# Proto-v2_1_-_TO-92.net
KiCad netlist of a schematic drawn in EAGLE
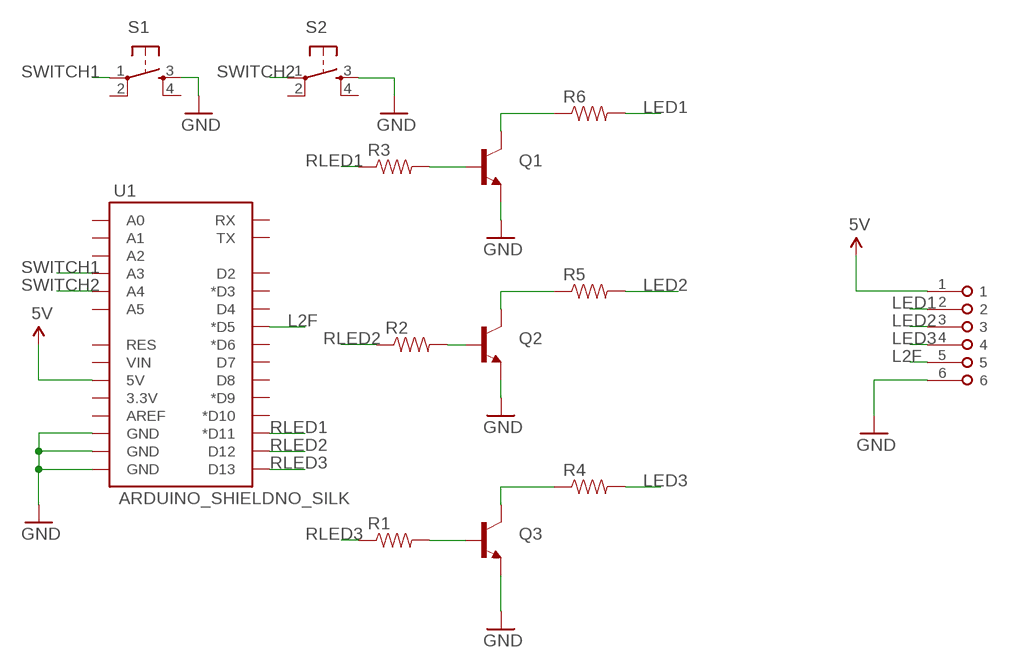
[diagram p0: schematic, sheet 1]

(export (version "E")
  (design (tool "Eeschema 10.0.6"))
  (components
    (comp (ref "Q1")
      (value "TRANSISTOR_NPNBC547")
      (footprint "eagle-import:TO-92-AMMO")
      (libsource (lib "eagle-import") (part "TRANSISTOR_NPNBC547"))
    )
    (comp (ref "Q2")
      (value "TRANSISTOR_NPNBC547")
      (footprint "eagle-import:TO-92-AMMO")
      (libsource (lib "eagle-import") (part "TRANSISTOR_NPNBC547"))
    )
    (comp (ref "Q3")
      (value "TRANSISTOR_NPNBC547")
      (footprint "eagle-import:TO-92-AMMO")
      (libsource (lib "eagle-import") (part "TRANSISTOR_NPNBC547"))
    )
    (comp (ref "R1")
      (value "RESISTORAXIAL-0.3")
      (footprint "eagle-import:AXIAL-0.3")
      (libsource (lib "eagle-import") (part "RESISTORAXIAL-0.3"))
    )
    (comp (ref "R2")
      (value "RESISTORAXIAL-0.3")
      (footprint "eagle-import:AXIAL-0.3")
      (libsource (lib "eagle-import") (part "RESISTORAXIAL-0.3"))
    )
    (comp (ref "R3")
      (value "RESISTORAXIAL-0.3")
      (footprint "eagle-import:AXIAL-0.3")
      (libsource (lib "eagle-import") (part "RESISTORAXIAL-0.3"))
    )
    (comp (ref "R4")
      (value "RESISTORAXIAL-0.3")
      (footprint "eagle-import:AXIAL-0.3")
      (libsource (lib "eagle-import") (part "RESISTORAXIAL-0.3"))
    )
    (comp (ref "R5")
      (value "RESISTORAXIAL-0.3")
      (footprint "eagle-import:AXIAL-0.3")
      (libsource (lib "eagle-import") (part "RESISTORAXIAL-0.3"))
    )
    (comp (ref "R6")
      (value "RESISTORAXIAL-0.3")
      (footprint "eagle-import:AXIAL-0.3")
      (libsource (lib "eagle-import") (part "RESISTORAXIAL-0.3"))
    )
    (comp (ref "S1")
      (value "TAC_SWITCHPTH")
      (footprint "eagle-import:TACTILE-PTH")
      (libsource (lib "eagle-import") (part "TAC_SWITCHPTH"))
    )
    (comp (ref "S2")
      (value "TAC_SWITCHPTH")
      (footprint "eagle-import:TACTILE-PTH")
      (libsource (lib "eagle-import") (part "TAC_SWITCHPTH"))
    )
    (comp (ref "U$1")
      (value "TERMINAL-6")
      (footprint "eagle-import:MBE-156")
      (libsource (lib "eagle-import") (part "TERMINAL-6"))
    )
    (comp (ref "U1")
      (value "ARDUINO_SHIELDNO_SILK")
      (footprint "eagle-import:DUEMILANOVE_VIAS")
      (libsource (lib "eagle-import") (part "ARDUINO_SHIELDNO_SILK"))
    )
  )
  (nets
    (net (code "1") (name "/L2F") (class "Default")
      (node (ref "U$1") (pin "5") (pinfunction "5_5") (pintype "bidirectional"))
      (node (ref "U1") (pin "D5") (pinfunction "*D5_D5") (pintype "bidirectional"))
    )
    (net (code "2") (name "/LED1") (class "Default")
      (node (ref "R6") (pin "P$2") (pinfunction "2_P$2") (pintype "passive"))
      (node (ref "U$1") (pin "2") (pinfunction "2_2") (pintype "bidirectional"))
    )
    (net (code "3") (name "/LED2") (class "Default")
      (node (ref "R5") (pin "P$2") (pinfunction "2_P$2") (pintype "passive"))
      (node (ref "U$1") (pin "3") (pinfunction "3_3") (pintype "bidirectional"))
    )
    (net (code "4") (name "/LED3") (class "Default")
      (node (ref "R4") (pin "P$2") (pinfunction "2_P$2") (pintype "passive"))
      (node (ref "U$1") (pin "4") (pinfunction "4_4") (pintype "bidirectional"))
    )
    (net (code "5") (name "/RLED1") (class "Default")
      (node (ref "R3") (pin "P$1") (pinfunction "1_P$1") (pintype "passive"))
      (node (ref "U1") (pin "D11") (pinfunction "*D11_D11") (pintype "bidirectional"))
    )
    (net (code "6") (name "/RLED2") (class "Default")
      (node (ref "R2") (pin "P$1") (pinfunction "1_P$1") (pintype "passive"))
      (node (ref "U1") (pin "D12") (pinfunction "D12_D12") (pintype "bidirectional"))
    )
    (net (code "7") (name "/RLED3") (class "Default")
      (node (ref "R1") (pin "P$1") (pinfunction "1_P$1") (pintype "passive"))
      (node (ref "U1") (pin "D13") (pinfunction "D13_D13") (pintype "bidirectional"))
    )
    (net (code "8") (name "/SWITCH1") (class "Default")
      (node (ref "S1") (pin "1") (pinfunction "1_1") (pintype "passive"))
      (node (ref "U1") (pin "A3") (pinfunction "A3_A3") (pintype "bidirectional"))
    )
    (net (code "9") (name "/SWITCH2") (class "Default")
      (node (ref "S2") (pin "1") (pinfunction "1_1") (pintype "passive"))
      (node (ref "U1") (pin "A4") (pinfunction "A4_A4") (pintype "bidirectional"))
    )
    (net (code "10") (name "5V") (class "Default")
      (node (ref "U$1") (pin "1") (pinfunction "1_1") (pintype "bidirectional"))
      (node (ref "U1") (pin "5V") (pinfunction "5V_5V") (pintype "bidirectional"))
    )
    (net (code "11") (name "GND") (class "Default")
      (node (ref "Q1") (pin "3") (pinfunction "E_3") (pintype "passive"))
      (node (ref "Q2") (pin "3") (pinfunction "E_3") (pintype "passive"))
      (node (ref "Q3") (pin "3") (pinfunction "E_3") (pintype "passive"))
      (node (ref "S1") (pin "3") (pinfunction "3_3") (pintype "passive"))
      (node (ref "S2") (pin "3") (pinfunction "3_3") (pintype "passive"))
      (node (ref "U$1") (pin "6") (pinfunction "6_6") (pintype "bidirectional"))
      (node (ref "U1") (pin "GND@0") (pinfunction "GND_GND@0") (pintype "bidirectional"))
      (node (ref "U1") (pin "GND@1") (pinfunction "GND_GND@1") (pintype "bidirectional"))
      (node (ref "U1") (pin "GND@2") (pinfunction "GND_GND@2") (pintype "bidirectional"))
    )
    (net (code "12") (name "Net-(Q1-B)") (class "Default")
      (node (ref "Q1") (pin "2") (pinfunction "B_2") (pintype "passive"))
      (node (ref "R3") (pin "P$2") (pinfunction "2_P$2") (pintype "passive"))
    )
    (net (code "13") (name "Net-(Q1-C)") (class "Default")
      (node (ref "Q1") (pin "1") (pinfunction "C_1") (pintype "passive"))
      (node (ref "R6") (pin "P$1") (pinfunction "1_P$1") (pintype "passive"))
    )
    (net (code "14") (name "Net-(Q2-B)") (class "Default")
      (node (ref "Q2") (pin "2") (pinfunction "B_2") (pintype "passive"))
      (node (ref "R2") (pin "P$2") (pinfunction "2_P$2") (pintype "passive"))
    )
    (net (code "15") (name "Net-(Q2-C)") (class "Default")
      (node (ref "Q2") (pin "1") (pinfunction "C_1") (pintype "passive"))
      (node (ref "R5") (pin "P$1") (pinfunction "1_P$1") (pintype "passive"))
    )
    (net (code "16") (name "Net-(Q3-B)") (class "Default")
      (node (ref "Q3") (pin "2") (pinfunction "B_2") (pintype "passive"))
      (node (ref "R1") (pin "P$2") (pinfunction "2_P$2") (pintype "passive"))
    )
    (net (code "17") (name "Net-(Q3-C)") (class "Default")
      (node (ref "Q3") (pin "1") (pinfunction "C_1") (pintype "passive"))
      (node (ref "R4") (pin "P$1") (pinfunction "1_P$1") (pintype "passive"))
    )
    (net (code "18") (name "unconnected-(S1-Pad2)") (class "Default")
      (node (ref "S1") (pin "2") (pinfunction "2_2") (pintype "passive"))
    )
    (net (code "19") (name "unconnected-(S1-Pad4)") (class "Default")
      (node (ref "S1") (pin "4") (pinfunction "4_4") (pintype "passive"))
    )
    (net (code "20") (name "unconnected-(S2-Pad2)") (class "Default")
      (node (ref "S2") (pin "2") (pinfunction "2_2") (pintype "passive"))
    )
    (net (code "21") (name "unconnected-(S2-Pad4)") (class "Default")
      (node (ref "S2") (pin "4") (pinfunction "4_4") (pintype "passive"))
    )
    (net (code "22") (name "unconnected-(U1-*D3-PadD3)") (class "Default")
      (node (ref "U1") (pin "D3") (pinfunction "*D3_D3") (pintype "bidirectional"))
    )
    (net (code "23") (name "unconnected-(U1-*D6-PadD6)") (class "Default")
      (node (ref "U1") (pin "D6") (pinfunction "*D6_D6") (pintype "bidirectional"))
    )
    (net (code "24") (name "unconnected-(U1-*D9-PadD9)") (class "Default")
      (node (ref "U1") (pin "D9") (pinfunction "*D9_D9") (pintype "bidirectional"))
    )
    (net (code "25") (name "unconnected-(U1-*D10-PadD10)") (class "Default")
      (node (ref "U1") (pin "D10") (pinfunction "*D10_D10") (pintype "bidirectional"))
    )
    (net (code "26") (name "unconnected-(U1-Pad3.3V)") (class "Default")
      (node (ref "U1") (pin "3.3V") (pinfunction "3.3V_3.3V") (pintype "bidirectional"))
    )
    (net (code "27") (name "unconnected-(U1-PadA0)") (class "Default")
      (node (ref "U1") (pin "A0") (pinfunction "A0_A0") (pintype "bidirectional"))
    )
    (net (code "28") (name "unconnected-(U1-PadA1)") (class "Default")
      (node (ref "U1") (pin "A1") (pinfunction "A1_A1") (pintype "bidirectional"))
    )
    (net (code "29") (name "unconnected-(U1-PadA2)") (class "Default")
      (node (ref "U1") (pin "A2") (pinfunction "A2_A2") (pintype "bidirectional"))
    )
    (net (code "30") (name "unconnected-(U1-PadA5)") (class "Default")
      (node (ref "U1") (pin "A5") (pinfunction "A5_A5") (pintype "bidirectional"))
    )
    (net (code "31") (name "unconnected-(U1-PadAREF)") (class "Default")
      (node (ref "U1") (pin "AREF") (pinfunction "AREF_AREF") (pintype "bidirectional"))
    )
    (net (code "32") (name "unconnected-(U1-PadD2)") (class "Default")
      (node (ref "U1") (pin "D2") (pinfunction "D2_D2") (pintype "bidirectional"))
    )
    (net (code "33") (name "unconnected-(U1-PadD4)") (class "Default")
      (node (ref "U1") (pin "D4") (pinfunction "D4_D4") (pintype "bidirectional"))
    )
    (net (code "34") (name "unconnected-(U1-PadD7)") (class "Default")
      (node (ref "U1") (pin "D7") (pinfunction "D7_D7") (pintype "bidirectional"))
    )
    (net (code "35") (name "unconnected-(U1-PadD8)") (class "Default")
      (node (ref "U1") (pin "D8") (pinfunction "D8_D8") (pintype "bidirectional"))
    )
    (net (code "36") (name "unconnected-(U1-PadRES)") (class "Default")
      (node (ref "U1") (pin "RES") (pinfunction "RES_RES") (pintype "bidirectional"))
    )
    (net (code "37") (name "unconnected-(U1-PadRX)") (class "Default")
      (node (ref "U1") (pin "RX") (pinfunction "RX_RX") (pintype "bidirectional"))
    )
    (net (code "38") (name "unconnected-(U1-PadTX)") (class "Default")
      (node (ref "U1") (pin "TX") (pinfunction "TX_TX") (pintype "bidirectional"))
    )
    (net (code "39") (name "unconnected-(U1-PadVIN)") (class "Default")
      (node (ref "U1") (pin "VIN") (pinfunction "VIN_VIN") (pintype "bidirectional"))
    )
  )
)
